# Main.net
KiCad netlist of a schematic drawn in Altium Designer
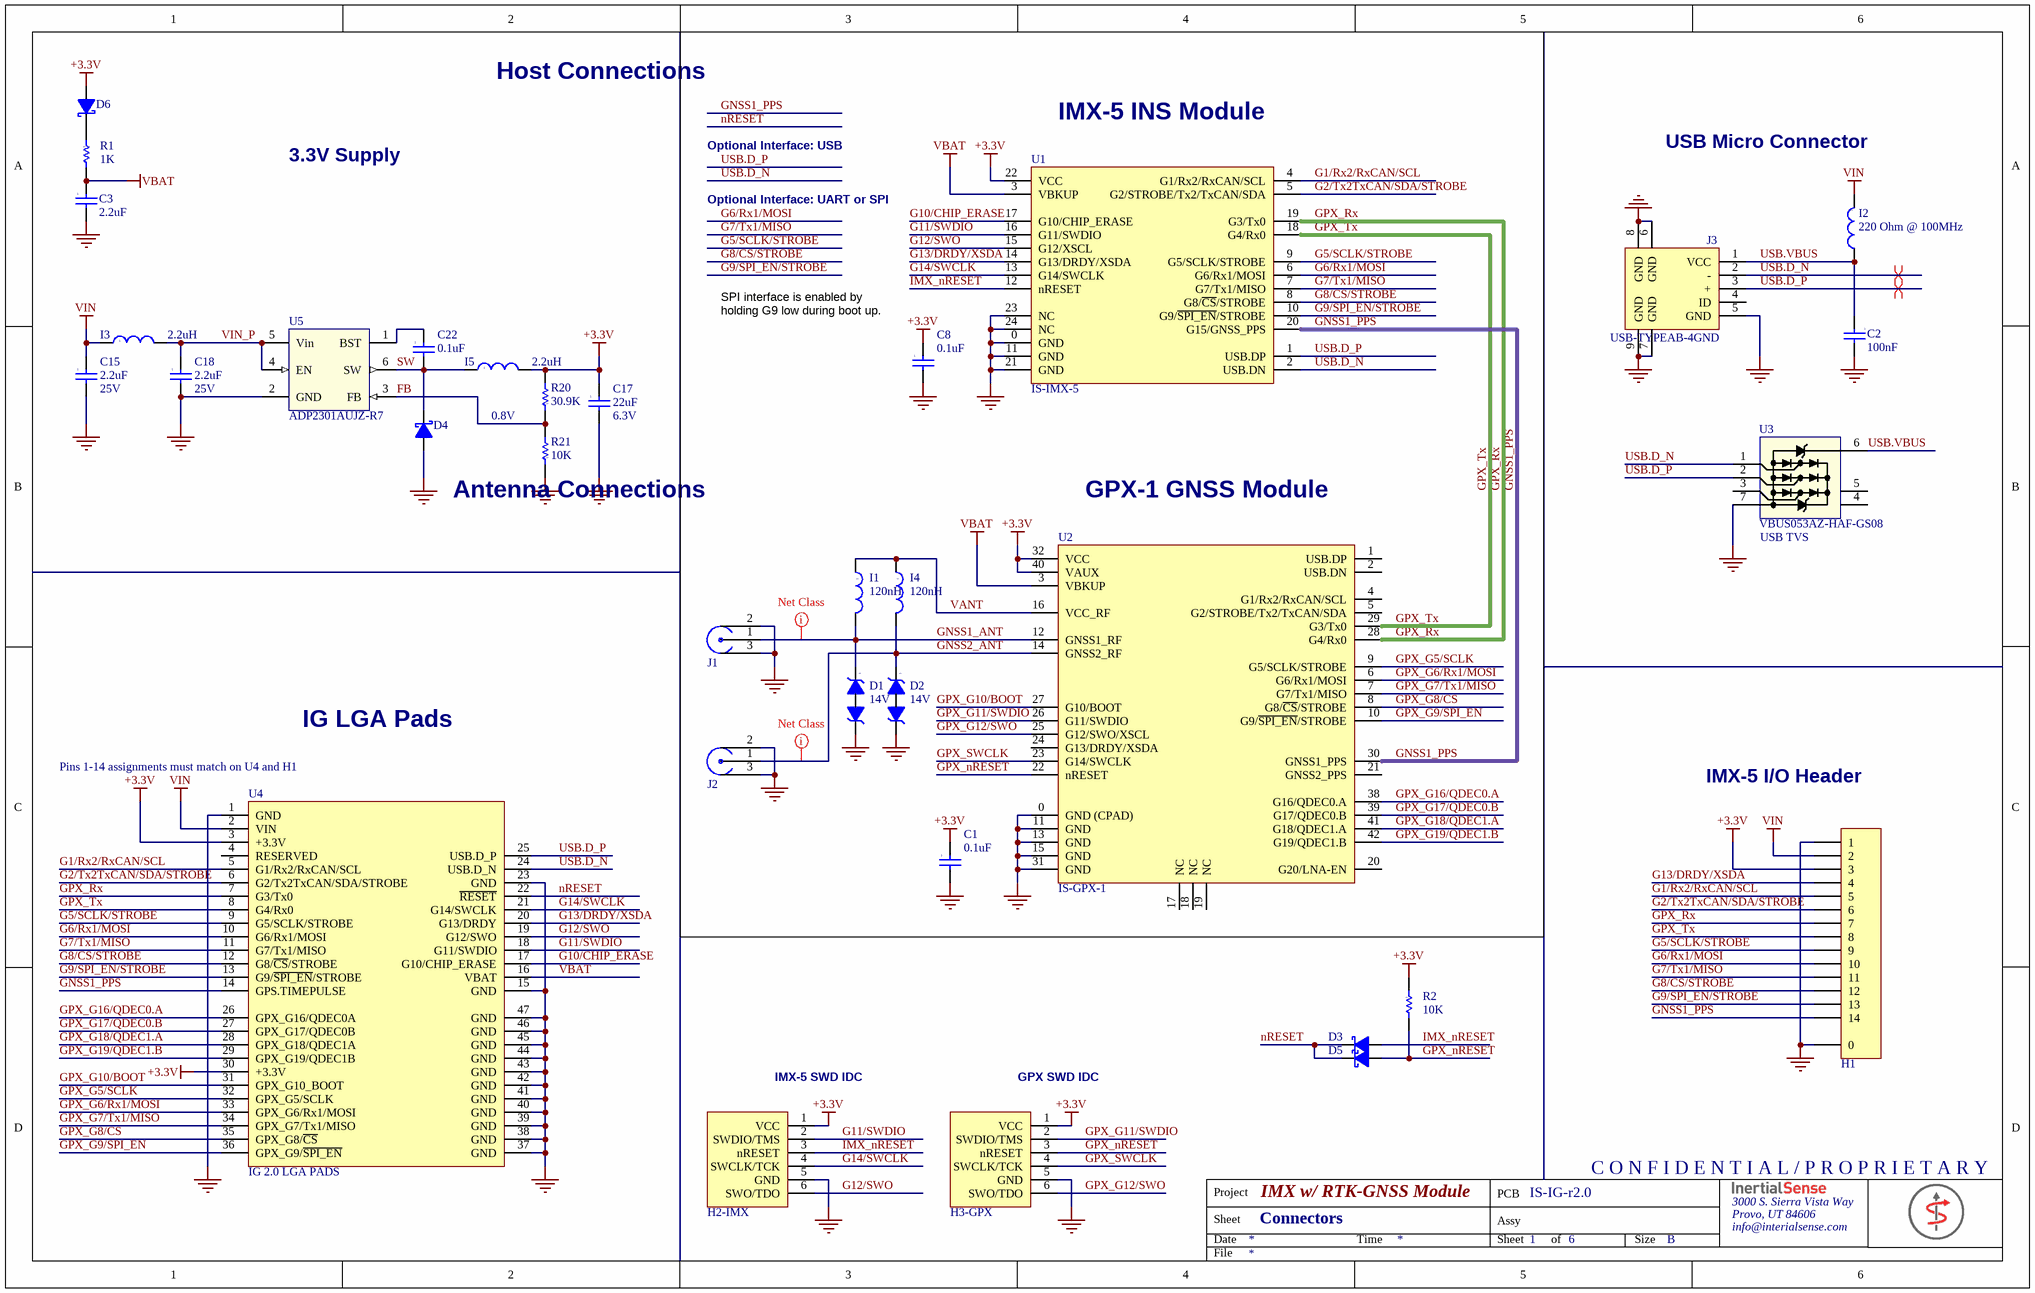
[diagram p0: Main.SchDoc]

(export (version "E")
  (design (tool "Eeschema 10.0.6"))
  (components
    (comp (ref "C1")
      (value "0.1uF")
      (footprint "0402")
      (description "CAP CER .10UF 50V X7R 10% 0402")
      (fields
        (field (name "MANUFACTURER") "TDK Corporation")
        (field (name "MANUFACTURER PART NUMBER") "C1005X7R1H104K")
        (field (name "PUBLISHER") "Altium Limited")
      )
      (libsource (lib "General") (part "Cap"))
    )
    (comp (ref "C2")
      (value "100nF")
      (footprint "0402")
      (description "CAP CER .10UF 50V X7R 10% 0402")
      (fields
        (field (name "MANUFACTURER") "TDK Corporation")
        (field (name "MANUFACTURER PART NUMBER") "C1005X7R1H104K")
        (field (name "PUBLISHER") "Altium Limited")
      )
      (libsource (lib "General") (part "Cap"))
    )
    (comp (ref "C3")
      (value "2.2uF")
      (footprint "0402")
      (description "0402 2.2 uF 6.3 V ±10% Tolerance X6S Multilayer Ceramic Capacitor")
      (fields
        (field (name "MANUFACTURER") "Murata")
        (field (name "MANUFACTURER PART NUMBER") "GRM155C80J225KE95D")
        (field (name "PUBLISHER") "Altium Limited")
      )
      (libsource (lib "General") (part "Cap"))
    )
    (comp (ref "C8")
      (value "0.1uF")
      (footprint "0402")
      (description "CAP CER .10UF 50V X7R 10% 0402")
      (fields
        (field (name "MANUFACTURER") "TDK Corporation")
        (field (name "MANUFACTURER PART NUMBER") "C1005X7R1H104K")
        (field (name "PUBLISHER") "Altium Limited")
      )
      (libsource (lib "General") (part "Cap"))
    )
    (comp (ref "C15")
      (value "2.2uF")
      (footprint "0603")
      (description "CAP CER 2.2UF 25V X6S 0603")
      (fields
        (field (name "MANUFACTURER") "Murata")
        (field (name "MANUFACTURER PART NUMBER") "GRT188C81E225KE13D")
        (field (name "VOLTAGE RATING") "25V")
        (field (name "PUBLISHER") "Altium Limited")
      )
      (libsource (lib "General") (part "Cap"))
    )
    (comp (ref "C17")
      (value "22uF")
      (footprint "0603")
      (description "CAP CER 22UF 6.3V X6S 0603")
      (fields
        (field (name "MANUFACTURER") "Murata")
        (field (name "MANUFACTURER PART NUMBER") "GRM188C80J226ME15D")
        (field (name "VOLTAGE RATING") "6.3V")
        (field (name "PUBLISHER") "Altium Limited")
      )
      (libsource (lib "General") (part "Cap"))
    )
    (comp (ref "C18")
      (value "2.2uF")
      (footprint "0603")
      (description "CAP CER 2.2UF 25V X6S 0603")
      (fields
        (field (name "MANUFACTURER") "Murata")
        (field (name "MANUFACTURER PART NUMBER") "GRT188C81E225KE13D")
        (field (name "VOLTAGE RATING") "25V")
        (field (name "PUBLISHER") "Altium Limited")
      )
      (libsource (lib "General") (part "Cap"))
    )
    (comp (ref "C22")
      (value "0.1uF")
      (footprint "0402")
      (description "CAP CER 0.1UF 50V X7R 0402")
      (fields
        (field (name "MANUFACTURER") "TDK")
        (field (name "MANUFACTURER PART NUMBER") "CGA2B3X7R1H104K050BB")
        (field (name "PUBLISHER") "Altium Limited")
      )
      (libsource (lib "General") (part "Cap"))
    )
    (comp (ref "D1")
      (value "Diode - Bidirectional Zener")
      (footprint "R0402")
      (description "LITTELFUSE - PESD0402-140 - DIODE, ESD PROTECTION, 0402, FULL REEL")
      (fields
        (field (name "MANUFACTURER") "Littelfuse")
        (field (name "MANUFACTURER PART NUMBER") "PESD0402-140")
        (field (name "WORKING VOLTAGE") "14V")
      )
      (libsource (lib "General") (part "Diode - Bidirectional Zener"))
    )
    (comp (ref "D2")
      (value "Diode - Bidirectional Zener")
      (footprint "R0402")
      (description "LITTELFUSE - PESD0402-140 - DIODE, ESD PROTECTION, 0402, FULL REEL")
      (fields
        (field (name "MANUFACTURER") "Littelfuse")
        (field (name "MANUFACTURER PART NUMBER") "PESD0402-140")
        (field (name "WORKING VOLTAGE") "14V")
      )
      (libsource (lib "General") (part "Diode - Bidirectional Zener"))
    )
    (comp (ref "D3")
      (value "Diode - Schottky")
      (footprint "D0402")
      (description "CDBQR0130L; SMT Schottky Diode; 35V 100mA; 2-Pin SOD-923F (0402)")
      (fields (field (name "MANUFACTURER") "Comchip") (field (name "MANUFACTURER PART NUMBER") "CDBQR0130L"))
      (libsource (lib "General") (part "Diode - Schottky"))
    )
    (comp (ref "D4")
      (value "Diode - Schottky")
      (footprint "D0603B")
      (description "DIODE SCHOTTKY 30V 2A 0603")
      (fields
        (field (name "MANUFACTURER") "Vishay")
        (field (name "MANUFACTURER PART NUMBER") "VSKY20301608-G4-08")
      )
      (libsource (lib "General") (part "Diode - Schottky"))
    )
    (comp (ref "D5")
      (value "Diode - Schottky")
      (footprint "D0402")
      (description "CDBQR0130L; SMT Schottky Diode; 35V 100mA; 2-Pin SOD-923F (0402)")
      (fields (field (name "MANUFACTURER") "Comchip") (field (name "MANUFACTURER PART NUMBER") "CDBQR0130L"))
      (libsource (lib "General") (part "Diode - Schottky"))
    )
    (comp (ref "D6")
      (value "Diode - Schottky")
      (footprint "D0603B")
      (description "DIODE SCHOTTKY 30V 2A 0603")
      (fields
        (field (name "MANUFACTURER") "Vishay")
        (field (name "MANUFACTURER PART NUMBER") "VSKY20301608-G4-08")
      )
      (libsource (lib "General") (part "Diode - Schottky"))
    )
    (comp (ref "H1")
      (value "Hdr - 14pin - mount")
      (footprint "SM14B-GHS-TB(LF)(SN)")
      (description "Conn Shrouded Header HDR 14 POS 1.25mm Solder ST Top Entry SMD T/R")
      (fields
        (field (name "MANUFACTURER") "JST")
        (field (name "MANUFACTURER PART NUMBER") "SM14B-GHS-TB(LF)(SN)")
      )
      (libsource (lib "Connectors") (part "Hdr - 14pin - mount"))
    )
    (comp (ref "H2-IMX")
      (value "TC2030-IDC")
      (footprint "TC2030-IDC-NL")
      (description "6 pin header")
      (libsource (lib "Connectors") (part "TC2030-IDC"))
    )
    (comp (ref "H3-GPX")
      (value "TC2030-IDC")
      (footprint "TC2030-IDC-NL")
      (description "6 pin header")
      (libsource (lib "Connectors") (part "TC2030-IDC"))
    )
    (comp (ref "I1")
      (value "120nH")
      (footprint "0402")
      (description "Inductor RF Chip Wirewound 120nH 5% 100MHz 20Q-Factor 110mA 2.66Ohm DCR 0402 Paper T/R")
      (fields
        (field (name "MANUFACTURER") "Murata")
        (field (name "MANUFACTURER PART NUMBER") "LQW15ANR12J00D")
      )
      (libsource (lib "General") (part "Inductor"))
    )
    (comp (ref "I2")
      (value "220 Ohm @ 100MHz")
      (footprint "I0603")
      (description "FERRITE CHIP 220 OHM 2500MA 0603")
      (fields
        (field (name "MANUFACTURER") "Murata Electronics North America")
        (field (name "MANUFACTURER PART NUMBER") "BLM18SG221TN1D")
      )
      (libsource (lib "") (part "Inductor_1"))
    )
    (comp (ref "I3")
      (value "2.2uH")
      (footprint "0806")
      (description "FIXED IND 2.2UH 1.2A 110 MOHM")
      (fields
        (field (name "MANUFACTURER") "TDK")
        (field (name "MANUFACTURER PART NUMBER") "MLP2016H2R2MT0S1")
      )
      (libsource (lib "General") (part "Inductor"))
    )
    (comp (ref "I4")
      (value "120nH")
      (footprint "0402")
      (description "Inductor RF Chip Wirewound 120nH 5% 100MHz 20Q-Factor 110mA 2.66Ohm DCR 0402 Paper T/R")
      (fields
        (field (name "MANUFACTURER") "Murata")
        (field (name "MANUFACTURER PART NUMBER") "LQW15ANR12J00D")
      )
      (libsource (lib "General") (part "Inductor"))
    )
    (comp (ref "I5")
      (value "2.2uH")
      (footprint "0806")
      (description "FIXED IND 2.2UH 1.2A 110 MOHM")
      (fields
        (field (name "MANUFACTURER") "TDK")
        (field (name "MANUFACTURER PART NUMBER") "MLP2016H2R2MT0S1")
      )
      (libsource (lib "General") (part "Inductor"))
    )
    (comp (ref "J1")
      (value "RF - GND x 2")
      (footprint "RF UMC SMD")
      (description "CONN UMC RCPT STR 50 OHM SMD")
      (fields
        (field (name "MANUFACTURER") "Emerson Network Power Connectivity Johnson")
        (field (name "MANUFACTURER PART NUMBER") "128-0711-201")
      )
      (libsource (lib "Connectors") (part "RF - GND x 2"))
    )
    (comp (ref "J2")
      (value "RF - GND x 2")
      (footprint "RF UMC SMD")
      (description "CONN UMC RCPT STR 50 OHM SMD")
      (fields
        (field (name "MANUFACTURER") "Emerson Network Power Connectivity Johnson")
        (field (name "MANUFACTURER PART NUMBER") "128-0711-201")
      )
      (libsource (lib "Connectors") (part "RF - GND x 2"))
    )
    (comp (ref "J3")
      (value "USB-TYPEAB-4GND")
      (footprint "USB Micro AB R/A THR")
      (description "CONN USB AB 4POS")
      (fields
        (field (name "MANUFACTURER") "Amphenol FCI")
        (field (name "MANUFACTURER PART NUMBER") "10118194-0001LF")
      )
      (libsource (lib "Connectors") (part "USB-TYPEAB-4GND"))
    )
    (comp (ref "R1")
      (value "1K")
      (footprint "R0402")
      (description "1 kOhms ±1% 0.063W, 1/16W Chip Resistor 0402 (1005 Metric) Moisture Resistant Thick Film")
      (fields
        (field (name "MANUFACTURER") "Yageo")
        (field (name "MANUFACTURER PART NUMBER") "RC0402FR-071KL")
      )
      (libsource (lib "General") (part "Res"))
    )
    (comp (ref "R2")
      (value "10K")
      (footprint "R0402")
      (description "1 kOhms ±1% 0.063W, 1/16W Chip Resistor 0402 (1005 Metric) Moisture Resistant Thick Film")
      (fields
        (field (name "MANUFACTURER") "Stackpole Electronics")
        (field (name "MANUFACTURER PART NUMBER") "RMCF0402FT10K0")
      )
      (libsource (lib "General") (part "Res"))
    )
    (comp (ref "R20")
      (value "30.9K")
      (footprint "R0402")
      (description "RES TF 30.9K OHM 1% 1/16W 0402")
      (fields
        (field (name "MANUFACTURER") "Stackpole Electronics Inc")
        (field (name "MANUFACTURER PART NUMBER") "RMCF0402FT30K9")
      )
      (libsource (lib "General") (part "Res"))
    )
    (comp (ref "R21")
      (value "10K")
      (footprint "R0402")
      (description "RES 10.0K OHM 1/16W 1% 0402 SMD")
      (fields
        (field (name "MANUFACTURER") "Yageo")
        (field (name "MANUFACTURER PART NUMBER") "RC0402FR-0710KL")
      )
      (libsource (lib "General") (part "Res"))
    )
    (comp (ref "U1")
      (value "IMX")
      (footprint "IS-IMX-5.0")
      (description "Inertial Sense IMX")
      (fields
        (field (name "MANUFACTURER") "Inertial Sense")
        (field (name "MANUFACTURER PART NUMBER") "IS-IMX-5")
      )
      (libsource (lib "IS-IMX-5") (part "IS-IMX-5.0"))
    )
    (comp (ref "U2")
      (value "GPX")
      (footprint "IS-GPX-1.0")
      (description "Inertial Sense GPX")
      (fields
        (field (name "MANUFACTURER") "Inertial Sense")
        (field (name "MANUFACTURER PART NUMBER") "IS-GPX-1")
      )
      (libsource (lib "IS-GPX-1") (part "IS-GPX-1.0"))
    )
    (comp (ref "U3")
      (value "VBUS053")
      (footprint "QFN50P160X160X60-6N")
      (description "ESD SUPPRESS 5.5V 36W 3-Line USB")
      (fields
        (field (name "MANUFACTURER") "Vishay Semiconductors")
        (field (name "MANUFACTURER PART NUMBER") "VBUS053AZ-HAF-GS08")
      )
      (libsource (lib "ICs") (part "VBUS053"))
    )
    (comp (ref "U4")
      (value "IG 2.0 LGA PADS")
      (footprint "IG-2.0_LGA")
      (description "IMX multi-frequency RTK-GNSS Module")
      (libsource (lib "Sensors") (part "IG_2.0_LGA"))
    )
    (comp (ref "U5")
      (value "ADP2301")
      (footprint "MO-178-AB")
      (description "IC BUCK ADJ 1.2A 6TSOT")
      (fields
        (field (name "MANUFACTURER") "Analog Devices Inc")
        (field (name "MANUFACTURER PART NUMBER") "ADP2301AUJZ-R7")
      )
      (libsource (lib "ICs") (part "ADP2301"))
    )
  )
  (nets
    (net (code "1") (name "+3.3V") (class "Default")
      (node (ref "C1") (pin "1") (pinfunction "1_1") (pintype "passive"))
      (node (ref "C17") (pin "1") (pinfunction "1_1") (pintype "passive"))
      (node (ref "C8") (pin "1") (pinfunction "1_1") (pintype "passive"))
      (node (ref "D6") (pin "A") (pinfunction "A_A") (pintype "passive"))
      (node (ref "H1") (pin "3") (pinfunction "3_3") (pintype "passive"))
      (node (ref "H2-IMX") (pin "1") (pinfunction "VCC_1") (pintype "passive"))
      (node (ref "H3-GPX") (pin "1") (pinfunction "VCC_1") (pintype "passive"))
      (node (ref "I5") (pin "2") (pinfunction "2_2") (pintype "passive"))
      (node (ref "R2") (pin "1") (pinfunction "1_1") (pintype "passive"))
      (node (ref "R20") (pin "2") (pinfunction "2_2") (pintype "passive"))
      (node (ref "U1") (pin "22") (pinfunction "VCC_22") (pintype "power_in"))
      (node (ref "U2") (pin "32") (pinfunction "VCC_32") (pintype "power_in"))
      (node (ref "U2") (pin "40") (pinfunction "VAUX_40") (pintype "power_in"))
      (node (ref "U4") (pin "3") (pinfunction "+3.3V_3") (pintype "passive"))
      (node (ref "U4") (pin "30") (pinfunction "+3.3V_30") (pintype "passive"))
    )
    (net (code "2") (name "/FB") (class "Default")
      (node (ref "R20") (pin "1") (pinfunction "1_1") (pintype "passive"))
      (node (ref "R21") (pin "2") (pinfunction "2_2") (pintype "passive"))
      (node (ref "U5") (pin "3") (pinfunction "FB_3") (pintype "input"))
    )
    (net (code "3") (name "/G1{slash}Rx2{slash}RxCAN{slash}SCL") (class "Default")
      (node (ref "H1") (pin "5") (pinfunction "5_5") (pintype "passive"))
      (node (ref "U1") (pin "4") (pinfunction "G1/Rx2/RxCAN/SCL_4") (pintype "passive"))
      (node (ref "U4") (pin "5") (pinfunction "G1/Rx2/RxCAN/SCL_5") (pintype "passive"))
    )
    (net (code "4") (name "/G2{slash}Tx2TxCAN{slash}SDA{slash}STROBE") (class "Default")
      (node (ref "H1") (pin "6") (pinfunction "6_6") (pintype "passive"))
      (node (ref "U1") (pin "5") (pinfunction "G2/STROBE/Tx2/TxCAN/SDA_5") (pintype "passive"))
      (node (ref "U4") (pin "6") (pinfunction "G2/Tx2TxCAN/SDA/STROBE_6") (pintype "passive"))
    )
    (net (code "5") (name "/G5{slash}SCLK{slash}STROBE") (class "Default")
      (node (ref "H1") (pin "9") (pinfunction "9_9") (pintype "passive"))
      (node (ref "U1") (pin "9") (pinfunction "G5/SCLK/STROBE_9") (pintype "passive"))
      (node (ref "U4") (pin "9") (pinfunction "G5/SCLK/STROBE_9") (pintype "passive"))
    )
    (net (code "6") (name "/G6{slash}Rx1{slash}MOSI") (class "Default")
      (node (ref "H1") (pin "10") (pinfunction "10_10") (pintype "passive"))
      (node (ref "U1") (pin "6") (pinfunction "G6/Rx1/MOSI_6") (pintype "passive"))
      (node (ref "U4") (pin "10") (pinfunction "G6/Rx1/MOSI_10") (pintype "passive"))
    )
    (net (code "7") (name "/G7{slash}Tx1{slash}MISO") (class "Default")
      (node (ref "H1") (pin "11") (pinfunction "11_11") (pintype "passive"))
      (node (ref "U1") (pin "7") (pinfunction "G7/Tx1/MISO_7") (pintype "passive"))
      (node (ref "U4") (pin "11") (pinfunction "G7/Tx1/MISO_11") (pintype "passive"))
    )
    (net (code "8") (name "/G8{slash}~{CS}{slash}STROBE") (class "Default")
      (node (ref "H1") (pin "12") (pinfunction "12_12") (pintype "passive"))
      (node (ref "U1") (pin "8") (pinfunction "G8/~{CS}/STROBE_8") (pintype "passive"))
      (node (ref "U4") (pin "12") (pinfunction "G8/~{CS}/STROBE_12") (pintype "passive"))
    )
    (net (code "9") (name "/G9{slash}~{SPI_EN}{slash}STROBE") (class "Default")
      (node (ref "H1") (pin "13") (pinfunction "13_13") (pintype "passive"))
      (node (ref "U1") (pin "10") (pinfunction "G9/~{SPI_EN}/STROBE_10") (pintype "passive"))
      (node (ref "U4") (pin "13") (pinfunction "G9/~{SPI_EN}/STROBE_13") (pintype "passive"))
    )
    (net (code "10") (name "/G10{slash}CHIP_ERASE") (class "Default")
      (node (ref "U1") (pin "17") (pinfunction "G10/CHIP_ERASE_17") (pintype "passive"))
      (node (ref "U4") (pin "17") (pinfunction "G10/CHIP_ERASE_17") (pintype "passive"))
    )
    (net (code "11") (name "/G11{slash}SWDIO") (class "Default")
      (node (ref "H2-IMX") (pin "2") (pinfunction "SWDIO/TMS_2") (pintype "passive"))
      (node (ref "U1") (pin "16") (pinfunction "G11/SWDIO_16") (pintype "passive"))
      (node (ref "U4") (pin "18") (pinfunction "G11/SWDIO_18") (pintype "passive"))
    )
    (net (code "12") (name "/G12{slash}SWO") (class "Default")
      (node (ref "H2-IMX") (pin "6") (pinfunction "SWO/TDO_6") (pintype "passive"))
      (node (ref "U1") (pin "15") (pinfunction "G12/XSCL_15") (pintype "passive"))
      (node (ref "U4") (pin "19") (pinfunction "G12/SWO_19") (pintype "passive"))
    )
    (net (code "13") (name "/G13{slash}DRDY{slash}XSDA") (class "Default")
      (node (ref "H1") (pin "4") (pinfunction "4_4") (pintype "passive"))
      (node (ref "U1") (pin "14") (pinfunction "G13/DRDY/XSDA_14") (pintype "passive"))
      (node (ref "U4") (pin "20") (pinfunction "G13/DRDY_20") (pintype "passive"))
    )
    (net (code "14") (name "/G14{slash}SWCLK") (class "Default")
      (node (ref "H2-IMX") (pin "4") (pinfunction "SWCLK/TCK_4") (pintype "passive"))
      (node (ref "U1") (pin "13") (pinfunction "G14/SWCLK_13") (pintype "passive"))
      (node (ref "U4") (pin "21") (pinfunction "G14/SWCLK_21") (pintype "passive"))
    )
    (net (code "15") (name "/GNSS1_ANT") (class "Default")
      (node (ref "D1") (pin "1") (pinfunction "1_1") (pintype "passive"))
      (node (ref "I1") (pin "2") (pinfunction "2_2") (pintype "passive"))
      (node (ref "J1") (pin "1") (pinfunction "1_1") (pintype "passive"))
      (node (ref "U2") (pin "12") (pinfunction "GNSS1_RF_12") (pintype "passive"))
    )
    (net (code "16") (name "/GNSS1_PPS") (class "Default")
      (node (ref "H1") (pin "14") (pinfunction "14_14") (pintype "passive"))
      (node (ref "U1") (pin "20") (pinfunction "G15/GNSS_PPS_20") (pintype "passive"))
      (node (ref "U2") (pin "30") (pinfunction "GNSS1_PPS_30") (pintype "passive"))
      (node (ref "U4") (pin "14") (pinfunction "GPS.TIMEPULSE_14") (pintype "passive"))
    )
    (net (code "17") (name "/GNSS2_ANT") (class "Default")
      (node (ref "D2") (pin "1") (pinfunction "1_1") (pintype "passive"))
      (node (ref "I4") (pin "2") (pinfunction "2_2") (pintype "passive"))
      (node (ref "J2") (pin "1") (pinfunction "1_1") (pintype "passive"))
      (node (ref "U2") (pin "14") (pinfunction "GNSS2_RF_14") (pintype "passive"))
    )
    (net (code "18") (name "/GPX_G5{slash}SCLK") (class "Default")
      (node (ref "U2") (pin "9") (pinfunction "G5/SCLK/STROBE_9") (pintype "passive"))
      (node (ref "U4") (pin "32") (pinfunction "GPX_G5/SCLK_32") (pintype "passive"))
    )
    (net (code "19") (name "/GPX_G6{slash}Rx1{slash}MOSI") (class "Default")
      (node (ref "U2") (pin "6") (pinfunction "G6/Rx1/MOSI_6") (pintype "passive"))
      (node (ref "U4") (pin "33") (pinfunction "GPX_G6/Rx1/MOSI_33") (pintype "passive"))
    )
    (net (code "20") (name "/GPX_G7{slash}Tx1{slash}MISO") (class "Default")
      (node (ref "U2") (pin "7") (pinfunction "G7/Tx1/MISO_7") (pintype "passive"))
      (node (ref "U4") (pin "34") (pinfunction "GPX_G7/Tx1/MISO_34") (pintype "passive"))
    )
    (net (code "21") (name "/GPX_G8{slash}~{CS}") (class "Default")
      (node (ref "U2") (pin "8") (pinfunction "G8/~{CS}/STROBE_8") (pintype "passive"))
      (node (ref "U4") (pin "35") (pinfunction "GPX_G8/~{CS}_35") (pintype "passive"))
    )
    (net (code "22") (name "/GPX_G9{slash}~{SPI_EN}") (class "Default")
      (node (ref "U2") (pin "10") (pinfunction "G9/~{SPI_EN}/STROBE_10") (pintype "passive"))
      (node (ref "U4") (pin "36") (pinfunction "GPX_G9/~{SPI_EN}_36") (pintype "passive"))
    )
    (net (code "23") (name "/GPX_G10{slash}BOOT") (class "Default")
      (node (ref "U2") (pin "27") (pinfunction "G10/BOOT_27") (pintype "passive"))
      (node (ref "U4") (pin "31") (pinfunction "GPX_G10_BOOT_31") (pintype "passive"))
    )
    (net (code "24") (name "/GPX_G11{slash}SWDIO") (class "Default")
      (node (ref "H3-GPX") (pin "2") (pinfunction "SWDIO/TMS_2") (pintype "passive"))
      (node (ref "U2") (pin "26") (pinfunction "G11/SWDIO_26") (pintype "passive"))
    )
    (net (code "25") (name "/GPX_G12{slash}SWO") (class "Default")
      (node (ref "H3-GPX") (pin "6") (pinfunction "SWO/TDO_6") (pintype "passive"))
      (node (ref "U2") (pin "25") (pinfunction "G12/SWO/XSCL_25") (pintype "passive"))
    )
    (net (code "26") (name "/GPX_G16{slash}QDEC0.A") (class "Default")
      (node (ref "U2") (pin "38") (pinfunction "G16/QDEC0.A_38") (pintype "passive"))
      (node (ref "U4") (pin "26") (pinfunction "GPX_G16/QDEC0A_26") (pintype "passive"))
    )
    (net (code "27") (name "/GPX_G17{slash}QDEC0.B") (class "Default")
      (node (ref "U2") (pin "39") (pinfunction "G17/QDEC0.B_39") (pintype "passive"))
      (node (ref "U4") (pin "27") (pinfunction "GPX_G17/QDEC0B_27") (pintype "passive"))
    )
    (net (code "28") (name "/GPX_G18{slash}QDEC1.A") (class "Default")
      (node (ref "U2") (pin "41") (pinfunction "G18/QDEC1.A_41") (pintype "passive"))
      (node (ref "U4") (pin "28") (pinfunction "GPX_G18/QDEC1A_28") (pintype "passive"))
    )
    (net (code "29") (name "/GPX_G19{slash}QDEC1.B") (class "Default")
      (node (ref "U2") (pin "42") (pinfunction "G19/QDEC1.B_42") (pintype "passive"))
      (node (ref "U4") (pin "29") (pinfunction "GPX_G19/QDEC1B_29") (pintype "passive"))
    )
    (net (code "30") (name "/GPX_Rx") (class "Default")
      (node (ref "H1") (pin "7") (pinfunction "7_7") (pintype "passive"))
      (node (ref "U1") (pin "19") (pinfunction "G3/Tx0_19") (pintype "passive"))
      (node (ref "U2") (pin "28") (pinfunction "G4/Rx0_28") (pintype "passive"))
      (node (ref "U4") (pin "7") (pinfunction "G3/Tx0_7") (pintype "passive"))
    )
    (net (code "31") (name "/GPX_SWCLK") (class "Default")
      (node (ref "H3-GPX") (pin "4") (pinfunction "SWCLK/TCK_4") (pintype "passive"))
      (node (ref "U2") (pin "23") (pinfunction "G14/SWCLK_23") (pintype "passive"))
    )
    (net (code "32") (name "/GPX_Tx") (class "Default")
      (node (ref "H1") (pin "8") (pinfunction "8_8") (pintype "passive"))
      (node (ref "U1") (pin "18") (pinfunction "G4/Rx0_18") (pintype "passive"))
      (node (ref "U2") (pin "29") (pinfunction "G3/Tx0_29") (pintype "passive"))
      (node (ref "U4") (pin "8") (pinfunction "G4/Rx0_8") (pintype "passive"))
    )
    (net (code "33") (name "/GPX_nRESET") (class "Default")
      (node (ref "D5") (pin "A") (pinfunction "A_A") (pintype "passive"))
      (node (ref "H3-GPX") (pin "3") (pinfunction "nRESET_3") (pintype "passive"))
      (node (ref "R2") (pin "2") (pinfunction "2_2") (pintype "passive"))
      (node (ref "U2") (pin "22") (pinfunction "nRESET_22") (pintype "passive"))
    )
    (net (code "34") (name "/IMX_nRESET") (class "Default")
      (node (ref "D3") (pin "A") (pinfunction "A_A") (pintype "passive"))
      (node (ref "H2-IMX") (pin "3") (pinfunction "nRESET_3") (pintype "passive"))
      (node (ref "U1") (pin "12") (pinfunction "nRESET_12") (pintype "passive"))
    )
    (net (code "35") (name "/SW") (class "Default")
      (node (ref "C22") (pin "2") (pinfunction "2_2") (pintype "passive"))
      (node (ref "D4") (pin "C") (pinfunction "C_C") (pintype "passive"))
      (node (ref "I5") (pin "1") (pinfunction "1_1") (pintype "passive"))
      (node (ref "U5") (pin "6") (pinfunction "SW_6") (pintype "output"))
    )
    (net (code "36") (name "/USB.D_N") (class "Default")
      (node (ref "J3") (pin "2") (pinfunction "-_2") (pintype "passive"))
      (node (ref "U1") (pin "2") (pinfunction "USB.DN_2") (pintype "passive"))
      (node (ref "U3") (pin "1") (pintype "passive"))
      (node (ref "U4") (pin "24") (pinfunction "USB.D_N_24") (pintype "passive"))
    )
    (net (code "37") (name "/USB.D_P") (class "Default")
      (node (ref "J3") (pin "3") (pinfunction "+_3") (pintype "passive"))
      (node (ref "U1") (pin "1") (pinfunction "USB.DP_1") (pintype "passive"))
      (node (ref "U3") (pin "2") (pintype "passive"))
      (node (ref "U4") (pin "25") (pinfunction "USB.D_P_25") (pintype "passive"))
    )
    (net (code "38") (name "/USB.VBUS") (class "Default")
      (node (ref "C2") (pin "1") (pinfunction "1_1") (pintype "passive"))
      (node (ref "I2") (pin "2") (pinfunction "2_2") (pintype "passive"))
      (node (ref "J3") (pin "1") (pinfunction "VCC_1") (pintype "passive"))
      (node (ref "U3") (pin "6") (pintype "passive"))
    )
    (net (code "39") (name "/VANT") (class "Default")
      (node (ref "I1") (pin "1") (pinfunction "1_1") (pintype "passive"))
      (node (ref "I4") (pin "1") (pinfunction "1_1") (pintype "passive"))
      (node (ref "U2") (pin "16") (pinfunction "VCC_RF_16") (pintype "power_in"))
    )
    (net (code "40") (name "/VIN_P") (class "Default")
      (node (ref "C18") (pin "1") (pinfunction "1_1") (pintype "passive"))
      (node (ref "I3") (pin "2") (pinfunction "2_2") (pintype "passive"))
      (node (ref "U5") (pin "4") (pinfunction "EN_4") (pintype "input"))
      (node (ref "U5") (pin "5") (pinfunction "Vin_5") (pintype "power_in"))
    )
    (net (code "41") (name "/nRESET") (class "Default")
      (node (ref "D3") (pin "C") (pinfunction "C_C") (pintype "passive"))
      (node (ref "D5") (pin "C") (pinfunction "C_C") (pintype "passive"))
      (node (ref "U4") (pin "22") (pinfunction "~{RESET}_22") (pintype "passive"))
    )
    (net (code "42") (name "GND") (class "Default")
      (node (ref "C1") (pin "2") (pinfunction "2_2") (pintype "passive"))
      (node (ref "C15") (pin "2") (pinfunction "2_2") (pintype "passive"))
      (node (ref "C17") (pin "2") (pinfunction "2_2") (pintype "passive"))
      (node (ref "C18") (pin "2") (pinfunction "2_2") (pintype "passive"))
      (node (ref "C2") (pin "2") (pinfunction "2_2") (pintype "passive"))
      (node (ref "C3") (pin "2") (pinfunction "2_2") (pintype "passive"))
      (node (ref "C8") (pin "2") (pinfunction "2_2") (pintype "passive"))
      (node (ref "D1") (pin "2") (pinfunction "2_2") (pintype "passive"))
      (node (ref "D2") (pin "2") (pinfunction "2_2") (pintype "passive"))
      (node (ref "D4") (pin "A") (pinfunction "A_A") (pintype "passive"))
      (node (ref "H1") (pin "0") (pinfunction "0_0") (pintype "passive"))
      (node (ref "H1") (pin "1") (pinfunction "1_1") (pintype "passive"))
      (node (ref "H2-IMX") (pin "5") (pinfunction "GND_5") (pintype "passive"))
      (node (ref "H3-GPX") (pin "5") (pinfunction "GND_5") (pintype "passive"))
      (node (ref "J1") (pin "2") (pinfunction "2_2") (pintype "passive"))
      (node (ref "J1") (pin "3") (pinfunction "3_3") (pintype "passive"))
      (node (ref "J2") (pin "2") (pinfunction "2_2") (pintype "passive"))
      (node (ref "J2") (pin "3") (pinfunction "3_3") (pintype "passive"))
      (node (ref "J3") (pin "5") (pinfunction "GND_5") (pintype "passive"))
      (node (ref "J3") (pin "6") (pinfunction "GND_6") (pintype "passive"))
      (node (ref "J3") (pin "7") (pinfunction "GND_7") (pintype "passive"))
      (node (ref "J3") (pin "8") (pinfunction "GND_8") (pintype "passive"))
      (node (ref "J3") (pin "9") (pinfunction "GND_9") (pintype "passive"))
      (node (ref "R21") (pin "1") (pinfunction "1_1") (pintype "passive"))
      (node (ref "U1") (pin "0") (pinfunction "GND_0") (pintype "power_in"))
      (node (ref "U1") (pin "11") (pinfunction "GND_11") (pintype "power_in"))
      (node (ref "U1") (pin "21") (pinfunction "GND_21") (pintype "power_in"))
      (node (ref "U1") (pin "23") (pinfunction "NC_23") (pintype "power_in"))
      (node (ref "U1") (pin "24") (pinfunction "NC_24") (pintype "power_in"))
      (node (ref "U2") (pin "0") (pinfunction "GND_(CPAD)_0") (pintype "power_in"))
      (node (ref "U2") (pin "11") (pinfunction "GND_11") (pintype "power_in"))
      (node (ref "U2") (pin "13") (pinfunction "GND_13") (pintype "power_in"))
      (node (ref "U2") (pin "15") (pinfunction "GND_15") (pintype "power_in"))
      (node (ref "U2") (pin "31") (pinfunction "GND_31") (pintype "power_in"))
      (node (ref "U3") (pin "7") (pintype "passive"))
      (node (ref "U4") (pin "1") (pinfunction "GND_1") (pintype "passive"))
      (node (ref "U4") (pin "15") (pinfunction "GND_15") (pintype "passive"))
      (node (ref "U4") (pin "23") (pinfunction "GND_23") (pintype "passive"))
      (node (ref "U4") (pin "37") (pinfunction "GND_37") (pintype "passive"))
      (node (ref "U4") (pin "38") (pinfunction "GND_38") (pintype "passive"))
      (node (ref "U4") (pin "39") (pinfunction "GND_39") (pintype "passive"))
      (node (ref "U4") (pin "40") (pinfunction "GND_40") (pintype "passive"))
      (node (ref "U4") (pin "41") (pinfunction "GND_41") (pintype "passive"))
      (node (ref "U4") (pin "42") (pinfunction "GND_42") (pintype "passive"))
      (node (ref "U4") (pin "43") (pinfunction "GND_43") (pintype "passive"))
      (node (ref "U4") (pin "44") (pinfunction "GND_44") (pintype "passive"))
      (node (ref "U4") (pin "45") (pinfunction "GND_45") (pintype "passive"))
      (node (ref "U4") (pin "46") (pinfunction "GND_46") (pintype "passive"))
      (node (ref "U4") (pin "47") (pinfunction "GND_47") (pintype "passive"))
      (node (ref "U5") (pin "2") (pinfunction "GND_2") (pintype "power_in"))
    )
    (net (code "43") (name "Net-(D6-PadC)") (class "Default")
      (node (ref "D6") (pin "C") (pinfunction "C_C") (pintype "passive"))
      (node (ref "R1") (pin "1") (pinfunction "1_1") (pintype "passive"))
    )
    (net (code "44") (name "Net-(U5-BST)") (class "Default")
      (node (ref "C22") (pin "1") (pinfunction "1_1") (pintype "passive"))
      (node (ref "U5") (pin "1") (pinfunction "BST_1") (pintype "passive"))
    )
    (net (code "45") (name "VBAT") (class "Default")
      (node (ref "C3") (pin "1") (pinfunction "1_1") (pintype "passive"))
      (node (ref "R1") (pin "2") (pinfunction "2_2") (pintype "passive"))
      (node (ref "U1") (pin "3") (pinfunction "VBKUP_3") (pintype "passive"))
      (node (ref "U2") (pin "3") (pinfunction "VBKUP_3") (pintype "passive"))
      (node (ref "U4") (pin "16") (pinfunction "VBAT_16") (pintype "passive"))
    )
    (net (code "46") (name "VIN") (class "Default")
      (node (ref "C15") (pin "1") (pinfunction "1_1") (pintype "passive"))
      (node (ref "H1") (pin "2") (pinfunction "2_2") (pintype "passive"))
      (node (ref "I2") (pin "1") (pinfunction "1_1") (pintype "passive"))
      (node (ref "I3") (pin "1") (pinfunction "1_1") (pintype "passive"))
      (node (ref "U4") (pin "2") (pinfunction "VIN_2") (pintype "passive"))
    )
    (net (code "47") (name "unconnected-(J3-ID-Pad4)") (class "Default")
      (node (ref "J3") (pin "4") (pinfunction "ID_4") (pintype "passive"))
    )
    (net (code "48") (name "unconnected-(U2-G1{slash}Rx2{slash}RxCAN{slash}SCL-Pad4)") (class "Default")
      (node (ref "U2") (pin "4") (pinfunction "G1/Rx2/RxCAN/SCL_4") (pintype "passive"))
    )
    (net (code "49") (name "unconnected-(U2-G2{slash}STROBE{slash}Tx2{slash}TxCAN{slash}SDA-Pad5)") (class "Default")
      (node (ref "U2") (pin "5") (pinfunction "G2/STROBE/Tx2/TxCAN/SDA_5") (pintype "passive"))
    )
    (net (code "50") (name "unconnected-(U2-G13{slash}DRDY{slash}XSDA-Pad24)") (class "Default")
      (node (ref "U2") (pin "24") (pinfunction "G13/DRDY/XSDA_24") (pintype "passive"))
    )
    (net (code "51") (name "unconnected-(U2-G20{slash}LNA-EN-Pad20)") (class "Default")
      (node (ref "U2") (pin "20") (pinfunction "G20/LNA-EN_20") (pintype "passive"))
    )
    (net (code "52") (name "unconnected-(U2-GNSS2_PPS-Pad21)") (class "Default")
      (node (ref "U2") (pin "21") (pinfunction "GNSS2_PPS_21") (pintype "passive"))
    )
    (net (code "53") (name "unconnected-(U2-NC-Pad17)") (class "Default")
      (node (ref "U2") (pin "17") (pinfunction "NC_17") (pintype "passive"))
    )
    (net (code "54") (name "unconnected-(U2-NC-Pad18)") (class "Default")
      (node (ref "U2") (pin "18") (pinfunction "NC_18") (pintype "passive"))
    )
    (net (code "55") (name "unconnected-(U2-NC-Pad19)") (class "Default")
      (node (ref "U2") (pin "19") (pinfunction "NC_19") (pintype "passive"))
    )
    (net (code "56") (name "unconnected-(U2-USB.DN-Pad2)") (class "Default")
      (node (ref "U2") (pin "2") (pinfunction "USB.DN_2") (pintype "passive"))
    )
    (net (code "57") (name "unconnected-(U2-USB.DP-Pad1)") (class "Default")
      (node (ref "U2") (pin "1") (pinfunction "USB.DP_1") (pintype "passive"))
    )
    (net (code "58") (name "unconnected-(U3-Pad3)") (class "Default")
      (node (ref "U3") (pin "3") (pintype "passive"))
    )
    (net (code "59") (name "unconnected-(U3-nc-Pad4)") (class "Default")
      (node (ref "U3") (pin "4") (pinfunction "nc_4") (pintype "passive"))
    )
    (net (code "60") (name "unconnected-(U3-nc-Pad5)") (class "Default")
      (node (ref "U3") (pin "5") (pinfunction "nc_5") (pintype "passive"))
    )
    (net (code "61") (name "unconnected-(U4-RESERVED-Pad4)") (class "Default")
      (node (ref "U4") (pin "4") (pinfunction "RESERVED_4") (pintype "passive"))
    )
  )
)
